# Grove-LED_Socket_Kit_v1_3.net
KiCad netlist of a schematic drawn in EAGLE
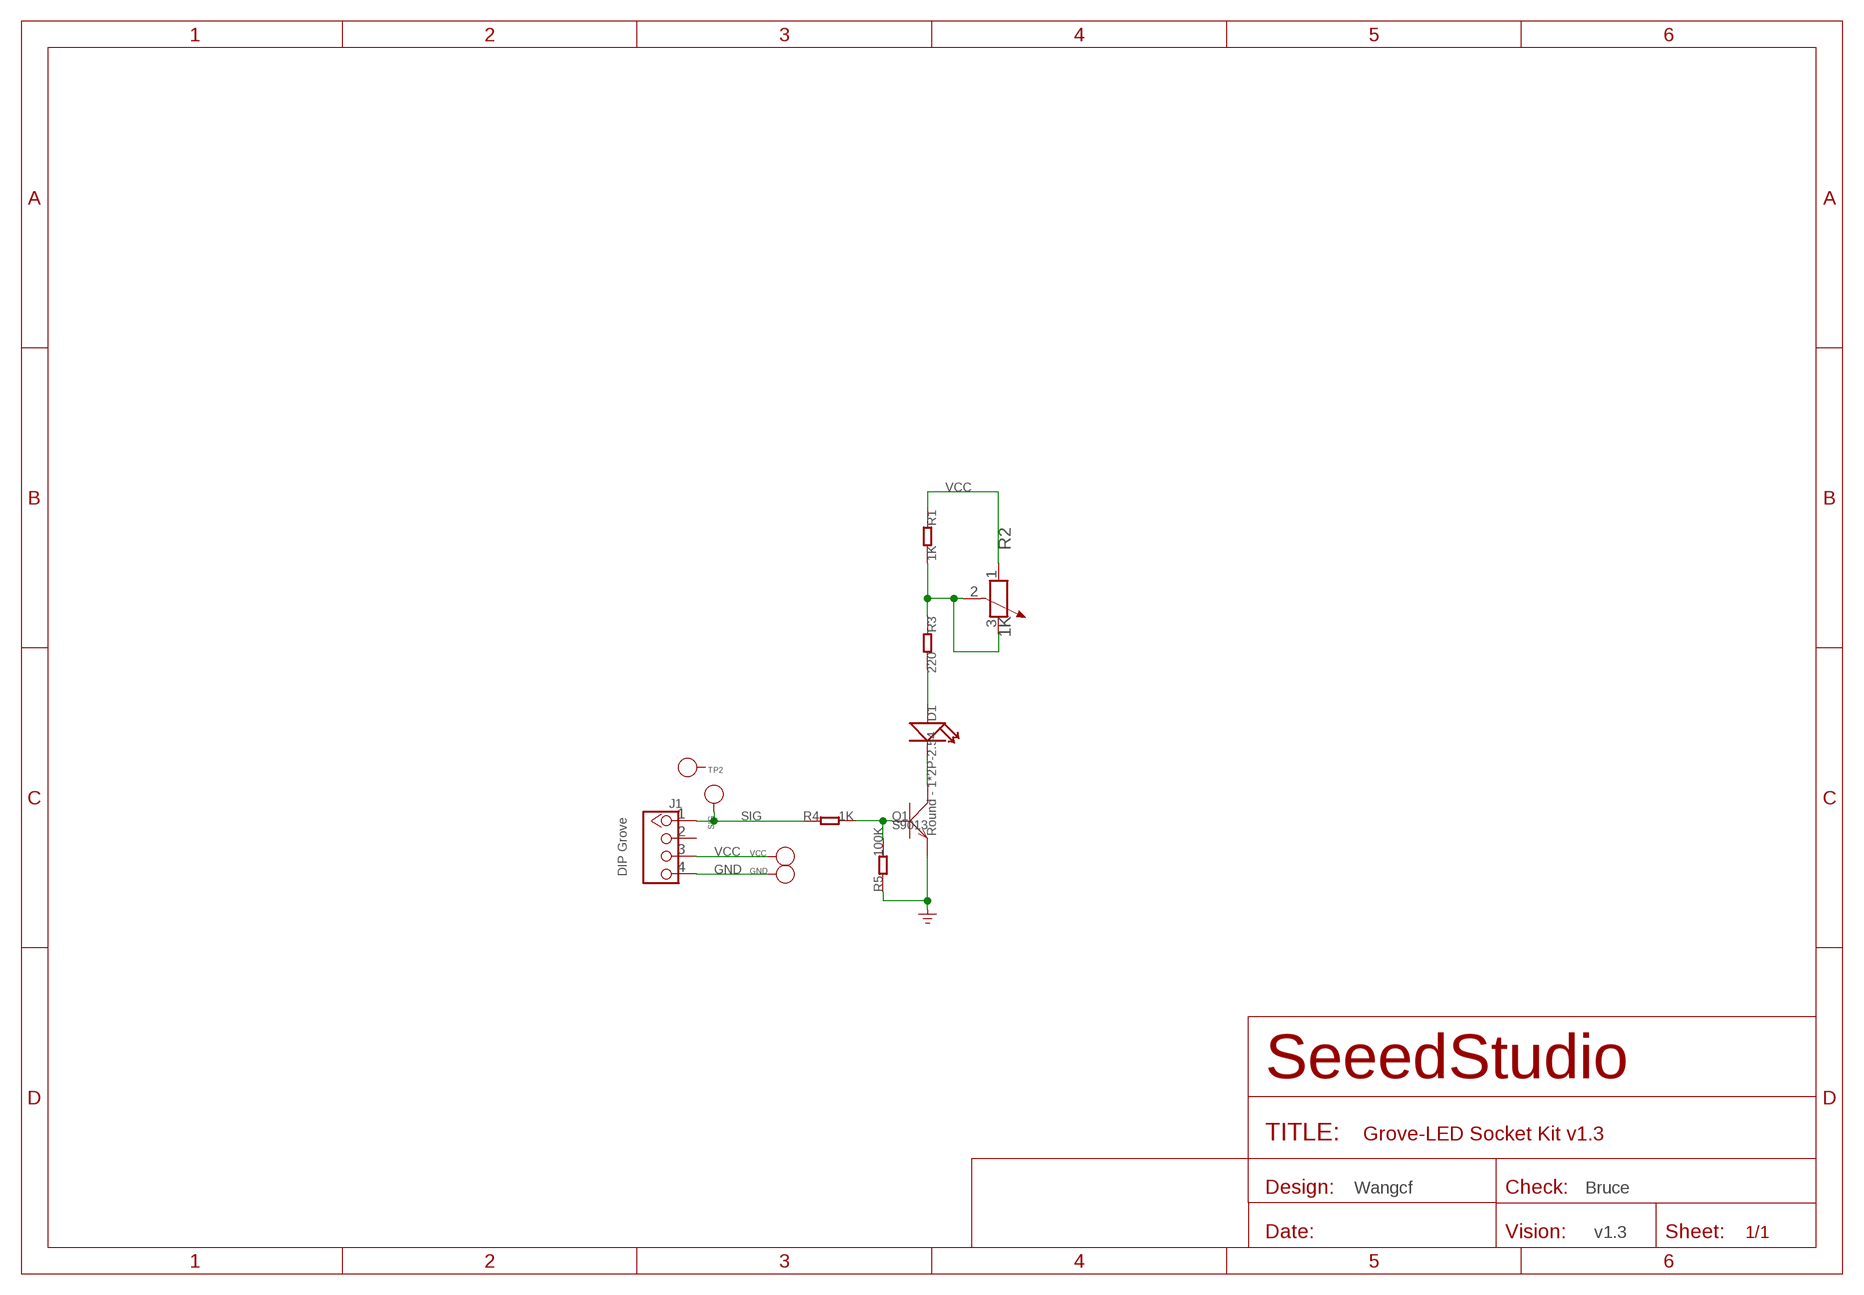
[diagram p0: schematic, sheet 1]

(export (version "E")
  (design (tool "Eeschema 10.0.6"))
  (components
    (comp (ref "D1")
      (value "Round - 1*2P-2.54")
      (footprint "eagle-import:LED-2P-2.54-6MM")
      (libsource (lib "eagle-import") (part "LED-6MM"))
    )
    (comp (ref "GND")
      (value "PAD-TEST-POINT'4545'")
      (footprint "eagle-import:TP_4545")
      (fields (field (name "PARTNO") "DNP"))
      (libsource (lib "eagle-import") (part "PAD-TEST-POINT'4545'"))
    )
    (comp (ref "J1")
      (value "DIP Grove")
      (footprint "eagle-import:2.0_1X4")
      (libsource (lib "eagle-import") (part "TWIG_2.0"))
    )
    (comp (ref "Q1")
      (value "S9013")
      (footprint "eagle-import:SOT23")
      (libsource (lib "eagle-import") (part "TRANSISTOR-NPN-SOT23"))
    )
    (comp (ref "R1")
      (value "1K")
      (footprint "eagle-import:0603")
      (libsource (lib "eagle-import") (part "005-R0603"))
    )
    (comp (ref "R2")
      (value "1K")
      (footprint "eagle-import:3P-SQUA-6.7X6.4")
      (libsource (lib "eagle-import") (part "R-POTENTIOMETER'EVN-D8A-A03-B'"))
    )
    (comp (ref "R3")
      (value "220")
      (footprint "eagle-import:0603")
      (libsource (lib "eagle-import") (part "005-R0603"))
    )
    (comp (ref "R4")
      (value "1K")
      (footprint "eagle-import:0603")
      (libsource (lib "eagle-import") (part "005-R0603"))
    )
    (comp (ref "R5")
      (value "100K")
      (footprint "eagle-import:0603")
      (libsource (lib "eagle-import") (part "005-R0603"))
    )
    (comp (ref "SIG")
      (value "PAD-TEST-POINT'4545'")
      (footprint "eagle-import:TP_4545")
      (fields (field (name "PARTNO") "DNP"))
      (libsource (lib "eagle-import") (part "PAD-TEST-POINT'4545'"))
    )
    (comp (ref "TP2")
      (value "PAD-TEST-POINT'4545'")
      (footprint "eagle-import:TP_4545")
      (fields (field (name "PARTNO") "DNP"))
      (libsource (lib "eagle-import") (part "PAD-TEST-POINT'4545'"))
    )
    (comp (ref "VCC")
      (value "PAD-TEST-POINT'4545'")
      (footprint "eagle-import:TP_4545")
      (fields (field (name "PARTNO") "DNP"))
      (libsource (lib "eagle-import") (part "PAD-TEST-POINT'4545'"))
    )
  )
  (nets
    (net (code "1") (name "/SIG") (class "Default")
      (node (ref "J1") (pin "1") (pinfunction "1_1") (pintype "bidirectional"))
      (node (ref "R4") (pin "1") (pinfunction "1_1") (pintype "passive"))
      (node (ref "SIG") (pin "T") (pinfunction "T_T") (pintype "bidirectional"))
    )
    (net (code "2") (name "/VCC") (class "Default")
      (node (ref "J1") (pin "3") (pinfunction "3_3") (pintype "bidirectional"))
      (node (ref "R1") (pin "1") (pinfunction "1_1") (pintype "passive"))
      (node (ref "R2") (pin "1") (pinfunction "1_1") (pintype "passive"))
      (node (ref "VCC") (pin "T") (pinfunction "T_T") (pintype "bidirectional"))
    )
    (net (code "3") (name "GND_POWER") (class "Default")
      (node (ref "GND") (pin "T") (pinfunction "T_T") (pintype "bidirectional"))
      (node (ref "J1") (pin "4") (pinfunction "4_4") (pintype "bidirectional"))
      (node (ref "Q1") (pin "2") (pinfunction "E_2") (pintype "passive"))
      (node (ref "R5") (pin "1") (pinfunction "1_1") (pintype "passive"))
    )
    (net (code "4") (name "Net-(D1-Pad+)") (class "Default")
      (node (ref "D1") (pin "+") (pinfunction "+_+") (pintype "passive"))
      (node (ref "R3") (pin "2") (pinfunction "2_2") (pintype "passive"))
    )
    (net (code "5") (name "Net-(Q1-B)") (class "Default")
      (node (ref "Q1") (pin "1") (pinfunction "B_1") (pintype "passive"))
      (node (ref "R4") (pin "2") (pinfunction "2_2") (pintype "passive"))
      (node (ref "R5") (pin "2") (pinfunction "2_2") (pintype "passive"))
    )
    (net (code "6") (name "Net-(Q1-C)") (class "Default")
      (node (ref "D1") (pin "-") (pinfunction "-_-") (pintype "passive"))
      (node (ref "Q1") (pin "3") (pinfunction "C_3") (pintype "passive"))
    )
    (net (code "7") (name "Net-(R2-2)") (class "Default")
      (node (ref "R1") (pin "2") (pinfunction "2_2") (pintype "passive"))
      (node (ref "R2") (pin "2") (pinfunction "3_2") (pintype "passive"))
      (node (ref "R2") (pin "3") (pinfunction "2_3") (pintype "passive"))
      (node (ref "R3") (pin "1") (pinfunction "1_1") (pintype "passive"))
    )
    (net (code "8") (name "unconnected-(J1-Pad2)") (class "Default")
      (node (ref "J1") (pin "2") (pinfunction "2_2") (pintype "bidirectional"))
    )
    (net (code "9") (name "unconnected-(TP2-PadT)") (class "Default")
      (node (ref "TP2") (pin "T") (pinfunction "T_T") (pintype "bidirectional"))
    )
  )
)
